# povsheild.net
KiCad netlist of a schematic drawn in EAGLE
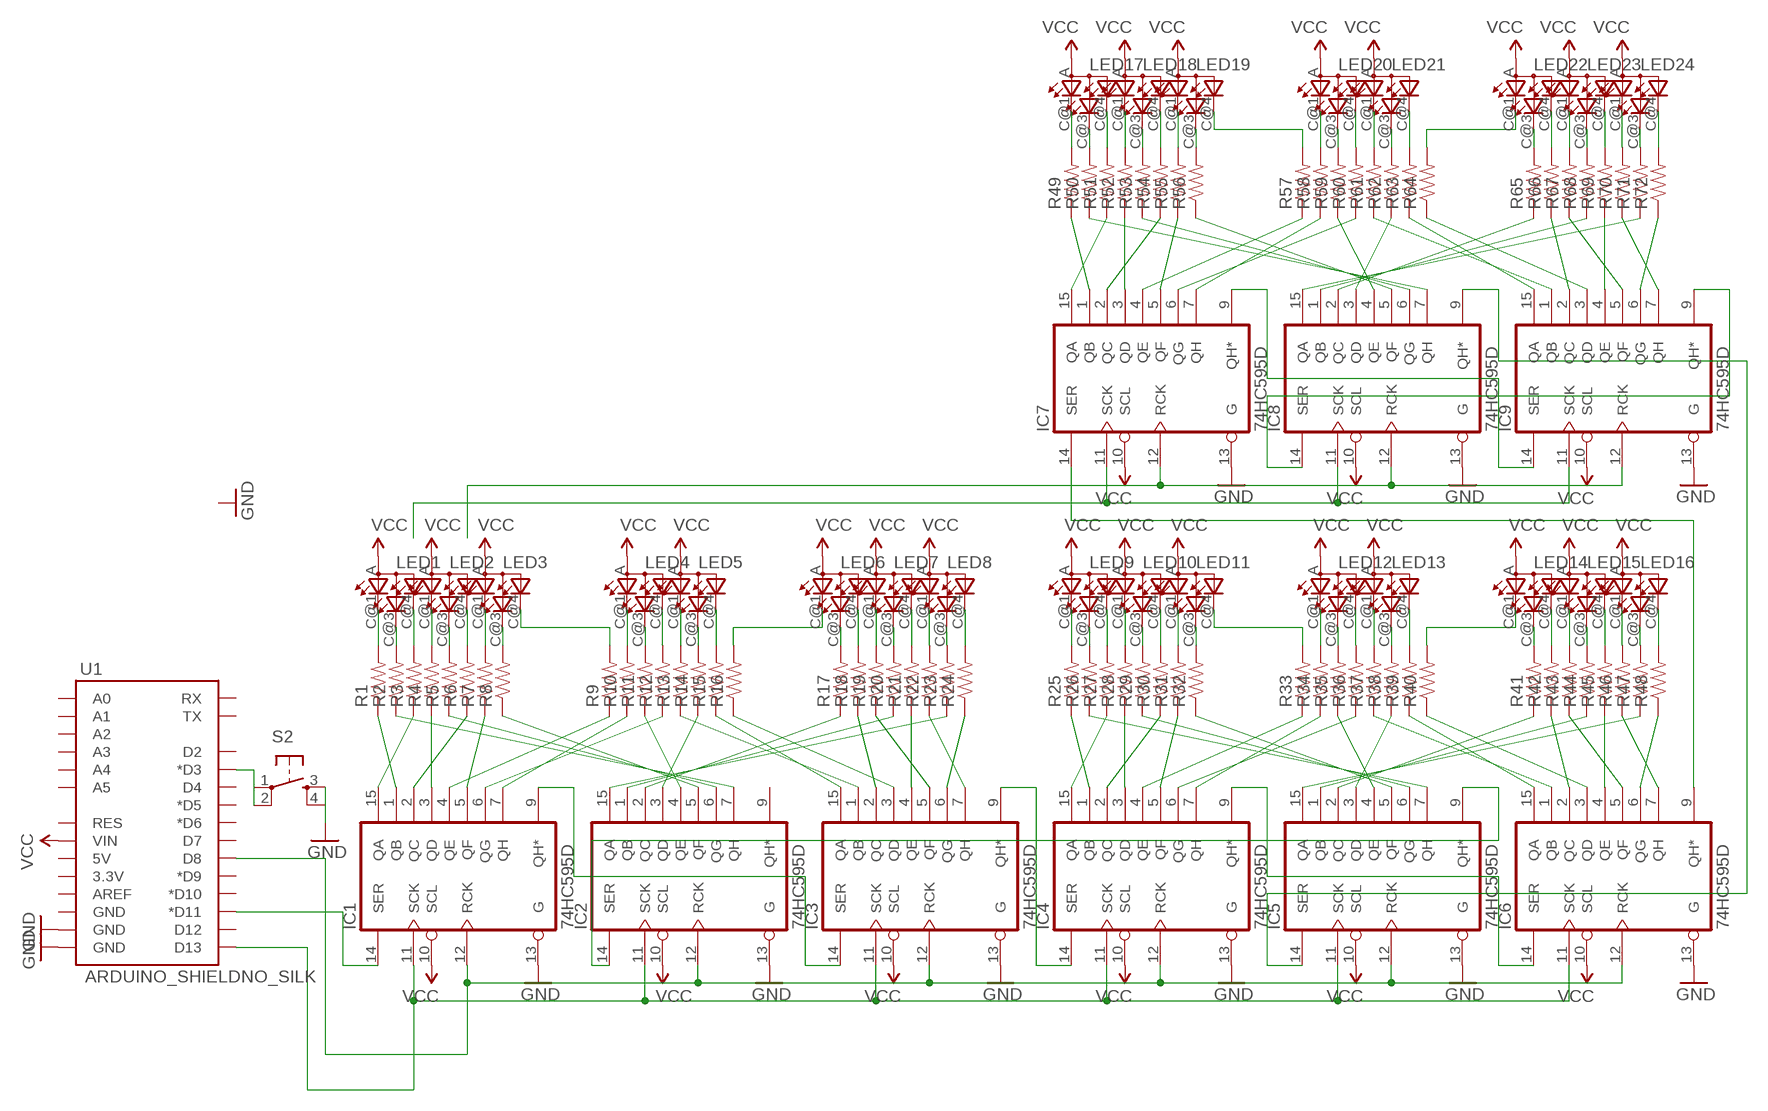
[diagram p0: schematic, sheet 1]

(export (version "E")
  (design (tool "Eeschema 10.0.6"))
  (components
    (comp (ref "IC1")
      (value "74HC595D")
      (footprint "eagle-import:SO16")
      (libsource (lib "eagle-import") (part "74595DHC"))
    )
    (comp (ref "IC2")
      (value "74HC595D")
      (footprint "eagle-import:SO16")
      (libsource (lib "eagle-import") (part "74595DHC"))
    )
    (comp (ref "IC3")
      (value "74HC595D")
      (footprint "eagle-import:SO16")
      (libsource (lib "eagle-import") (part "74595DHC"))
    )
    (comp (ref "IC4")
      (value "74HC595D")
      (footprint "eagle-import:SO16")
      (libsource (lib "eagle-import") (part "74595DHC"))
    )
    (comp (ref "IC5")
      (value "74HC595D")
      (footprint "eagle-import:SO16")
      (libsource (lib "eagle-import") (part "74595DHC"))
    )
    (comp (ref "IC6")
      (value "74HC595D")
      (footprint "eagle-import:SO16")
      (libsource (lib "eagle-import") (part "74595DHC"))
    )
    (comp (ref "IC7")
      (value "74HC595D")
      (footprint "eagle-import:SO16")
      (libsource (lib "eagle-import") (part "74595DHC"))
    )
    (comp (ref "IC8")
      (value "74HC595D")
      (footprint "eagle-import:SO16")
      (libsource (lib "eagle-import") (part "74595DHC"))
    )
    (comp (ref "IC9")
      (value "74HC595D")
      (footprint "eagle-import:SO16")
      (libsource (lib "eagle-import") (part "74595DHC"))
    )
    (comp (ref "LED1")
      (value "TOPLED-3P-LCC-4")
      (footprint "eagle-import:P-LCC-4")
      (libsource (lib "eagle-import") (part "TOPLED-3P-LCC-4"))
    )
    (comp (ref "LED2")
      (value "TOPLED-3P-LCC-4")
      (footprint "eagle-import:P-LCC-4")
      (libsource (lib "eagle-import") (part "TOPLED-3P-LCC-4"))
    )
    (comp (ref "LED3")
      (value "TOPLED-3P-LCC-4")
      (footprint "eagle-import:P-LCC-4")
      (libsource (lib "eagle-import") (part "TOPLED-3P-LCC-4"))
    )
    (comp (ref "LED4")
      (value "TOPLED-3P-LCC-4")
      (footprint "eagle-import:P-LCC-4")
      (libsource (lib "eagle-import") (part "TOPLED-3P-LCC-4"))
    )
    (comp (ref "LED5")
      (value "TOPLED-3P-LCC-4")
      (footprint "eagle-import:P-LCC-4")
      (libsource (lib "eagle-import") (part "TOPLED-3P-LCC-4"))
    )
    (comp (ref "LED6")
      (value "TOPLED-3P-LCC-4")
      (footprint "eagle-import:P-LCC-4")
      (libsource (lib "eagle-import") (part "TOPLED-3P-LCC-4"))
    )
    (comp (ref "LED7")
      (value "TOPLED-3P-LCC-4")
      (footprint "eagle-import:P-LCC-4")
      (libsource (lib "eagle-import") (part "TOPLED-3P-LCC-4"))
    )
    (comp (ref "LED8")
      (value "TOPLED-3P-LCC-4")
      (footprint "eagle-import:P-LCC-4")
      (libsource (lib "eagle-import") (part "TOPLED-3P-LCC-4"))
    )
    (comp (ref "LED9")
      (value "TOPLED-3P-LCC-4")
      (footprint "eagle-import:P-LCC-4")
      (libsource (lib "eagle-import") (part "TOPLED-3P-LCC-4"))
    )
    (comp (ref "LED10")
      (value "TOPLED-3P-LCC-4")
      (footprint "eagle-import:P-LCC-4")
      (libsource (lib "eagle-import") (part "TOPLED-3P-LCC-4"))
    )
    (comp (ref "LED11")
      (value "TOPLED-3P-LCC-4")
      (footprint "eagle-import:P-LCC-4")
      (libsource (lib "eagle-import") (part "TOPLED-3P-LCC-4"))
    )
    (comp (ref "LED12")
      (value "TOPLED-3P-LCC-4")
      (footprint "eagle-import:P-LCC-4")
      (libsource (lib "eagle-import") (part "TOPLED-3P-LCC-4"))
    )
    (comp (ref "LED13")
      (value "TOPLED-3P-LCC-4")
      (footprint "eagle-import:P-LCC-4")
      (libsource (lib "eagle-import") (part "TOPLED-3P-LCC-4"))
    )
    (comp (ref "LED14")
      (value "TOPLED-3P-LCC-4")
      (footprint "eagle-import:P-LCC-4")
      (libsource (lib "eagle-import") (part "TOPLED-3P-LCC-4"))
    )
    (comp (ref "LED15")
      (value "TOPLED-3P-LCC-4")
      (footprint "eagle-import:P-LCC-4")
      (libsource (lib "eagle-import") (part "TOPLED-3P-LCC-4"))
    )
    (comp (ref "LED16")
      (value "TOPLED-3P-LCC-4")
      (footprint "eagle-import:P-LCC-4")
      (libsource (lib "eagle-import") (part "TOPLED-3P-LCC-4"))
    )
    (comp (ref "LED17")
      (value "TOPLED-3P-LCC-4")
      (footprint "eagle-import:P-LCC-4")
      (libsource (lib "eagle-import") (part "TOPLED-3P-LCC-4"))
    )
    (comp (ref "LED18")
      (value "TOPLED-3P-LCC-4")
      (footprint "eagle-import:P-LCC-4")
      (libsource (lib "eagle-import") (part "TOPLED-3P-LCC-4"))
    )
    (comp (ref "LED19")
      (value "TOPLED-3P-LCC-4")
      (footprint "eagle-import:P-LCC-4")
      (libsource (lib "eagle-import") (part "TOPLED-3P-LCC-4"))
    )
    (comp (ref "LED20")
      (value "TOPLED-3P-LCC-4")
      (footprint "eagle-import:P-LCC-4")
      (libsource (lib "eagle-import") (part "TOPLED-3P-LCC-4"))
    )
    (comp (ref "LED21")
      (value "TOPLED-3P-LCC-4")
      (footprint "eagle-import:P-LCC-4")
      (libsource (lib "eagle-import") (part "TOPLED-3P-LCC-4"))
    )
    (comp (ref "LED22")
      (value "TOPLED-3P-LCC-4")
      (footprint "eagle-import:P-LCC-4")
      (libsource (lib "eagle-import") (part "TOPLED-3P-LCC-4"))
    )
    (comp (ref "LED23")
      (value "TOPLED-3P-LCC-4")
      (footprint "eagle-import:P-LCC-4")
      (libsource (lib "eagle-import") (part "TOPLED-3P-LCC-4"))
    )
    (comp (ref "LED24")
      (value "TOPLED-3P-LCC-4")
      (footprint "eagle-import:P-LCC-4")
      (libsource (lib "eagle-import") (part "TOPLED-3P-LCC-4"))
    )
    (comp (ref "R1")
      (value "RESISTOR0805-RES")
      (footprint "eagle-import:0805")
      (libsource (lib "eagle-import") (part "RESISTOR0805-RES"))
    )
    (comp (ref "R2")
      (value "RESISTOR0805-RES")
      (footprint "eagle-import:0805")
      (libsource (lib "eagle-import") (part "RESISTOR0805-RES"))
    )
    (comp (ref "R3")
      (value "RESISTOR0805-RES")
      (footprint "eagle-import:0805")
      (libsource (lib "eagle-import") (part "RESISTOR0805-RES"))
    )
    (comp (ref "R4")
      (value "RESISTOR0805-RES")
      (footprint "eagle-import:0805")
      (libsource (lib "eagle-import") (part "RESISTOR0805-RES"))
    )
    (comp (ref "R5")
      (value "RESISTOR0805-RES")
      (footprint "eagle-import:0805")
      (libsource (lib "eagle-import") (part "RESISTOR0805-RES"))
    )
    (comp (ref "R6")
      (value "RESISTOR0805-RES")
      (footprint "eagle-import:0805")
      (libsource (lib "eagle-import") (part "RESISTOR0805-RES"))
    )
    (comp (ref "R7")
      (value "RESISTOR0805-RES")
      (footprint "eagle-import:0805")
      (libsource (lib "eagle-import") (part "RESISTOR0805-RES"))
    )
    (comp (ref "R8")
      (value "RESISTOR0805-RES")
      (footprint "eagle-import:0805")
      (libsource (lib "eagle-import") (part "RESISTOR0805-RES"))
    )
    (comp (ref "R9")
      (value "RESISTOR0805-RES")
      (footprint "eagle-import:0805")
      (libsource (lib "eagle-import") (part "RESISTOR0805-RES"))
    )
    (comp (ref "R10")
      (value "RESISTOR0805-RES")
      (footprint "eagle-import:0805")
      (libsource (lib "eagle-import") (part "RESISTOR0805-RES"))
    )
    (comp (ref "R11")
      (value "RESISTOR0805-RES")
      (footprint "eagle-import:0805")
      (libsource (lib "eagle-import") (part "RESISTOR0805-RES"))
    )
    (comp (ref "R12")
      (value "RESISTOR0805-RES")
      (footprint "eagle-import:0805")
      (libsource (lib "eagle-import") (part "RESISTOR0805-RES"))
    )
    (comp (ref "R13")
      (value "RESISTOR0805-RES")
      (footprint "eagle-import:0805")
      (libsource (lib "eagle-import") (part "RESISTOR0805-RES"))
    )
    (comp (ref "R14")
      (value "RESISTOR0805-RES")
      (footprint "eagle-import:0805")
      (libsource (lib "eagle-import") (part "RESISTOR0805-RES"))
    )
    (comp (ref "R15")
      (value "RESISTOR0805-RES")
      (footprint "eagle-import:0805")
      (libsource (lib "eagle-import") (part "RESISTOR0805-RES"))
    )
    (comp (ref "R16")
      (value "RESISTOR0805-RES")
      (footprint "eagle-import:0805")
      (libsource (lib "eagle-import") (part "RESISTOR0805-RES"))
    )
    (comp (ref "R17")
      (value "RESISTOR0805-RES")
      (footprint "eagle-import:0805")
      (libsource (lib "eagle-import") (part "RESISTOR0805-RES"))
    )
    (comp (ref "R18")
      (value "RESISTOR0805-RES")
      (footprint "eagle-import:0805")
      (libsource (lib "eagle-import") (part "RESISTOR0805-RES"))
    )
    (comp (ref "R19")
      (value "RESISTOR0805-RES")
      (footprint "eagle-import:0805")
      (libsource (lib "eagle-import") (part "RESISTOR0805-RES"))
    )
    (comp (ref "R20")
      (value "RESISTOR0805-RES")
      (footprint "eagle-import:0805")
      (libsource (lib "eagle-import") (part "RESISTOR0805-RES"))
    )
    (comp (ref "R21")
      (value "RESISTOR0805-RES")
      (footprint "eagle-import:0805")
      (libsource (lib "eagle-import") (part "RESISTOR0805-RES"))
    )
    (comp (ref "R22")
      (value "RESISTOR0805-RES")
      (footprint "eagle-import:0805")
      (libsource (lib "eagle-import") (part "RESISTOR0805-RES"))
    )
    (comp (ref "R23")
      (value "RESISTOR0805-RES")
      (footprint "eagle-import:0805")
      (libsource (lib "eagle-import") (part "RESISTOR0805-RES"))
    )
    (comp (ref "R24")
      (value "RESISTOR0805-RES")
      (footprint "eagle-import:0805")
      (libsource (lib "eagle-import") (part "RESISTOR0805-RES"))
    )
    (comp (ref "R25")
      (value "RESISTOR0805-RES")
      (footprint "eagle-import:0805")
      (libsource (lib "eagle-import") (part "RESISTOR0805-RES"))
    )
    (comp (ref "R26")
      (value "RESISTOR0805-RES")
      (footprint "eagle-import:0805")
      (libsource (lib "eagle-import") (part "RESISTOR0805-RES"))
    )
    (comp (ref "R27")
      (value "RESISTOR0805-RES")
      (footprint "eagle-import:0805")
      (libsource (lib "eagle-import") (part "RESISTOR0805-RES"))
    )
    (comp (ref "R28")
      (value "RESISTOR0805-RES")
      (footprint "eagle-import:0805")
      (libsource (lib "eagle-import") (part "RESISTOR0805-RES"))
    )
    (comp (ref "R29")
      (value "RESISTOR0805-RES")
      (footprint "eagle-import:0805")
      (libsource (lib "eagle-import") (part "RESISTOR0805-RES"))
    )
    (comp (ref "R30")
      (value "RESISTOR0805-RES")
      (footprint "eagle-import:0805")
      (libsource (lib "eagle-import") (part "RESISTOR0805-RES"))
    )
    (comp (ref "R31")
      (value "RESISTOR0805-RES")
      (footprint "eagle-import:0805")
      (libsource (lib "eagle-import") (part "RESISTOR0805-RES"))
    )
    (comp (ref "R32")
      (value "RESISTOR0805-RES")
      (footprint "eagle-import:0805")
      (libsource (lib "eagle-import") (part "RESISTOR0805-RES"))
    )
    (comp (ref "R33")
      (value "RESISTOR0805-RES")
      (footprint "eagle-import:0805")
      (libsource (lib "eagle-import") (part "RESISTOR0805-RES"))
    )
    (comp (ref "R34")
      (value "RESISTOR0805-RES")
      (footprint "eagle-import:0805")
      (libsource (lib "eagle-import") (part "RESISTOR0805-RES"))
    )
    (comp (ref "R35")
      (value "RESISTOR0805-RES")
      (footprint "eagle-import:0805")
      (libsource (lib "eagle-import") (part "RESISTOR0805-RES"))
    )
    (comp (ref "R36")
      (value "RESISTOR0805-RES")
      (footprint "eagle-import:0805")
      (libsource (lib "eagle-import") (part "RESISTOR0805-RES"))
    )
    (comp (ref "R37")
      (value "RESISTOR0805-RES")
      (footprint "eagle-import:0805")
      (libsource (lib "eagle-import") (part "RESISTOR0805-RES"))
    )
    (comp (ref "R38")
      (value "RESISTOR0805-RES")
      (footprint "eagle-import:0805")
      (libsource (lib "eagle-import") (part "RESISTOR0805-RES"))
    )
    (comp (ref "R39")
      (value "RESISTOR0805-RES")
      (footprint "eagle-import:0805")
      (libsource (lib "eagle-import") (part "RESISTOR0805-RES"))
    )
    (comp (ref "R40")
      (value "RESISTOR0805-RES")
      (footprint "eagle-import:0805")
      (libsource (lib "eagle-import") (part "RESISTOR0805-RES"))
    )
    (comp (ref "R41")
      (value "RESISTOR0805-RES")
      (footprint "eagle-import:0805")
      (libsource (lib "eagle-import") (part "RESISTOR0805-RES"))
    )
    (comp (ref "R42")
      (value "RESISTOR0805-RES")
      (footprint "eagle-import:0805")
      (libsource (lib "eagle-import") (part "RESISTOR0805-RES"))
    )
    (comp (ref "R43")
      (value "RESISTOR0805-RES")
      (footprint "eagle-import:0805")
      (libsource (lib "eagle-import") (part "RESISTOR0805-RES"))
    )
    (comp (ref "R44")
      (value "RESISTOR0805-RES")
      (footprint "eagle-import:0805")
      (libsource (lib "eagle-import") (part "RESISTOR0805-RES"))
    )
    (comp (ref "R45")
      (value "RESISTOR0805-RES")
      (footprint "eagle-import:0805")
      (libsource (lib "eagle-import") (part "RESISTOR0805-RES"))
    )
    (comp (ref "R46")
      (value "RESISTOR0805-RES")
      (footprint "eagle-import:0805")
      (libsource (lib "eagle-import") (part "RESISTOR0805-RES"))
    )
    (comp (ref "R47")
      (value "RESISTOR0805-RES")
      (footprint "eagle-import:0805")
      (libsource (lib "eagle-import") (part "RESISTOR0805-RES"))
    )
    (comp (ref "R48")
      (value "RESISTOR0805-RES")
      (footprint "eagle-import:0805")
      (libsource (lib "eagle-import") (part "RESISTOR0805-RES"))
    )
    (comp (ref "R49")
      (value "RESISTOR0805-RES")
      (footprint "eagle-import:0805")
      (libsource (lib "eagle-import") (part "RESISTOR0805-RES"))
    )
    (comp (ref "R50")
      (value "RESISTOR0805-RES")
      (footprint "eagle-import:0805")
      (libsource (lib "eagle-import") (part "RESISTOR0805-RES"))
    )
    (comp (ref "R51")
      (value "RESISTOR0805-RES")
      (footprint "eagle-import:0805")
      (libsource (lib "eagle-import") (part "RESISTOR0805-RES"))
    )
    (comp (ref "R52")
      (value "RESISTOR0805-RES")
      (footprint "eagle-import:0805")
      (libsource (lib "eagle-import") (part "RESISTOR0805-RES"))
    )
    (comp (ref "R53")
      (value "RESISTOR0805-RES")
      (footprint "eagle-import:0805")
      (libsource (lib "eagle-import") (part "RESISTOR0805-RES"))
    )
    (comp (ref "R54")
      (value "RESISTOR0805-RES")
      (footprint "eagle-import:0805")
      (libsource (lib "eagle-import") (part "RESISTOR0805-RES"))
    )
    (comp (ref "R55")
      (value "RESISTOR0805-RES")
      (footprint "eagle-import:0805")
      (libsource (lib "eagle-import") (part "RESISTOR0805-RES"))
    )
    (comp (ref "R56")
      (value "RESISTOR0805-RES")
      (footprint "eagle-import:0805")
      (libsource (lib "eagle-import") (part "RESISTOR0805-RES"))
    )
    (comp (ref "R57")
      (value "RESISTOR0805-RES")
      (footprint "eagle-import:0805")
      (libsource (lib "eagle-import") (part "RESISTOR0805-RES"))
    )
    (comp (ref "R58")
      (value "RESISTOR0805-RES")
      (footprint "eagle-import:0805")
      (libsource (lib "eagle-import") (part "RESISTOR0805-RES"))
    )
    (comp (ref "R59")
      (value "RESISTOR0805-RES")
      (footprint "eagle-import:0805")
      (libsource (lib "eagle-import") (part "RESISTOR0805-RES"))
    )
    (comp (ref "R60")
      (value "RESISTOR0805-RES")
      (footprint "eagle-import:0805")
      (libsource (lib "eagle-import") (part "RESISTOR0805-RES"))
    )
    (comp (ref "R61")
      (value "RESISTOR0805-RES")
      (footprint "eagle-import:0805")
      (libsource (lib "eagle-import") (part "RESISTOR0805-RES"))
    )
    (comp (ref "R62")
      (value "RESISTOR0805-RES")
      (footprint "eagle-import:0805")
      (libsource (lib "eagle-import") (part "RESISTOR0805-RES"))
    )
    (comp (ref "R63")
      (value "RESISTOR0805-RES")
      (footprint "eagle-import:0805")
      (libsource (lib "eagle-import") (part "RESISTOR0805-RES"))
    )
    (comp (ref "R64")
      (value "RESISTOR0805-RES")
      (footprint "eagle-import:0805")
      (libsource (lib "eagle-import") (part "RESISTOR0805-RES"))
    )
    (comp (ref "R65")
      (value "RESISTOR0805-RES")
      (footprint "eagle-import:0805")
      (libsource (lib "eagle-import") (part "RESISTOR0805-RES"))
    )
    (comp (ref "R66")
      (value "RESISTOR0805-RES")
      (footprint "eagle-import:0805")
      (libsource (lib "eagle-import") (part "RESISTOR0805-RES"))
    )
    (comp (ref "R67")
      (value "RESISTOR0805-RES")
      (footprint "eagle-import:0805")
      (libsource (lib "eagle-import") (part "RESISTOR0805-RES"))
    )
    (comp (ref "R68")
      (value "RESISTOR0805-RES")
      (footprint "eagle-import:0805")
      (libsource (lib "eagle-import") (part "RESISTOR0805-RES"))
    )
    (comp (ref "R69")
      (value "RESISTOR0805-RES")
      (footprint "eagle-import:0805")
      (libsource (lib "eagle-import") (part "RESISTOR0805-RES"))
    )
    (comp (ref "R70")
      (value "RESISTOR0805-RES")
      (footprint "eagle-import:0805")
      (libsource (lib "eagle-import") (part "RESISTOR0805-RES"))
    )
    (comp (ref "R71")
      (value "RESISTOR0805-RES")
      (footprint "eagle-import:0805")
      (libsource (lib "eagle-import") (part "RESISTOR0805-RES"))
    )
    (comp (ref "R72")
      (value "RESISTOR0805-RES")
      (footprint "eagle-import:0805")
      (libsource (lib "eagle-import") (part "RESISTOR0805-RES"))
    )
    (comp (ref "S2")
      (value "TAC_SWITCHSMD")
      (footprint "eagle-import:TACTILE_SWITCH_SMD")
      (libsource (lib "eagle-import") (part "TAC_SWITCHSMD"))
    )
    (comp (ref "U1")
      (value "ARDUINO_SHIELDNO_SILK")
      (footprint "eagle-import:DUEMILANOVE_VIAS")
      (libsource (lib "eagle-import") (part "ARDUINO_SHIELDNO_SILK"))
    )
  )
  (nets
    (net (code "1") (name "/LATCH") (class "Default")
      (node (ref "IC1") (pin "12") (pinfunction "RCK_12") (pintype "input"))
      (node (ref "IC2") (pin "12") (pinfunction "RCK_12") (pintype "input"))
      (node (ref "IC3") (pin "12") (pinfunction "RCK_12") (pintype "input"))
      (node (ref "IC4") (pin "12") (pinfunction "RCK_12") (pintype "input"))
      (node (ref "IC5") (pin "12") (pinfunction "RCK_12") (pintype "input"))
      (node (ref "IC6") (pin "12") (pinfunction "RCK_12") (pintype "input"))
      (node (ref "IC7") (pin "12") (pinfunction "RCK_12") (pintype "input"))
      (node (ref "IC8") (pin "12") (pinfunction "RCK_12") (pintype "input"))
      (node (ref "IC9") (pin "12") (pinfunction "RCK_12") (pintype "input"))
      (node (ref "U1") (pin "D8") (pinfunction "D8_D8") (pintype "bidirectional"))
    )
    (net (code "2") (name "/SCK") (class "Default")
      (node (ref "IC1") (pin "11") (pinfunction "SCK_11") (pintype "input"))
      (node (ref "IC2") (pin "11") (pinfunction "SCK_11") (pintype "input"))
      (node (ref "IC3") (pin "11") (pinfunction "SCK_11") (pintype "input"))
      (node (ref "IC4") (pin "11") (pinfunction "SCK_11") (pintype "input"))
      (node (ref "IC5") (pin "11") (pinfunction "SCK_11") (pintype "input"))
      (node (ref "IC6") (pin "11") (pinfunction "SCK_11") (pintype "input"))
      (node (ref "IC7") (pin "11") (pinfunction "SCK_11") (pintype "input"))
      (node (ref "IC8") (pin "11") (pinfunction "SCK_11") (pintype "input"))
      (node (ref "IC9") (pin "11") (pinfunction "SCK_11") (pintype "input"))
      (node (ref "U1") (pin "D13") (pinfunction "D13_D13") (pintype "bidirectional"))
    )
    (net (code "3") (name "GND") (class "Default")
      (node (ref "IC1") (pin "13") (pinfunction "G_13") (pintype "input"))
      (node (ref "IC2") (pin "13") (pinfunction "G_13") (pintype "input"))
      (node (ref "IC3") (pin "13") (pinfunction "G_13") (pintype "input"))
      (node (ref "IC4") (pin "13") (pinfunction "G_13") (pintype "input"))
      (node (ref "IC5") (pin "13") (pinfunction "G_13") (pintype "input"))
      (node (ref "IC6") (pin "13") (pinfunction "G_13") (pintype "input"))
      (node (ref "IC7") (pin "13") (pinfunction "G_13") (pintype "input"))
      (node (ref "IC8") (pin "13") (pinfunction "G_13") (pintype "input"))
      (node (ref "IC9") (pin "13") (pinfunction "G_13") (pintype "input"))
      (node (ref "S2") (pin "3") (pinfunction "3_3") (pintype "passive"))
      (node (ref "S2") (pin "4") (pinfunction "4_4") (pintype "passive"))
      (node (ref "U1") (pin "GND@0") (pinfunction "GND_GND@0") (pintype "bidirectional"))
      (node (ref "U1") (pin "GND@1") (pinfunction "GND_GND@1") (pintype "bidirectional"))
    )
    (net (code "4") (name "Net-(IC1A-QA)") (class "Default")
      (node (ref "IC1") (pin "15") (pinfunction "QA_15") (pintype "tri_state"))
      (node (ref "R3") (pin "1") (pinfunction "1_1") (pintype "passive"))
    )
    (net (code "5") (name "Net-(IC1A-QB)") (class "Default")
      (node (ref "IC1") (pin "1") (pinfunction "QB_1") (pintype "tri_state"))
      (node (ref "R1") (pin "1") (pinfunction "1_1") (pintype "passive"))
    )
    (net (code "6") (name "Net-(IC1A-QC)") (class "Default")
      (node (ref "IC1") (pin "2") (pinfunction "QC_2") (pintype "tri_state"))
      (node (ref "R6") (pin "1") (pinfunction "1_1") (pintype "passive"))
    )
    (net (code "7") (name "Net-(IC1A-QD)") (class "Default")
      (node (ref "IC1") (pin "3") (pinfunction "QD_3") (pintype "tri_state"))
      (node (ref "R4") (pin "1") (pinfunction "1_1") (pintype "passive"))
    )
    (net (code "8") (name "Net-(IC1A-QE)") (class "Default")
      (node (ref "IC1") (pin "4") (pinfunction "QE_4") (pintype "tri_state"))
      (node (ref "R9") (pin "1") (pinfunction "1_1") (pintype "passive"))
    )
    (net (code "9") (name "Net-(IC1A-QF)") (class "Default")
      (node (ref "IC1") (pin "5") (pinfunction "QF_5") (pintype "tri_state"))
      (node (ref "R7") (pin "1") (pinfunction "1_1") (pintype "passive"))
    )
    (net (code "10") (name "Net-(IC1A-QG)") (class "Default")
      (node (ref "IC1") (pin "6") (pinfunction "QG_6") (pintype "tri_state"))
      (node (ref "R12") (pin "1") (pinfunction "1_1") (pintype "passive"))
    )
    (net (code "11") (name "Net-(IC1A-QH)") (class "Default")
      (node (ref "IC1") (pin "7") (pinfunction "QH_7") (pintype "tri_state"))
      (node (ref "R10") (pin "1") (pinfunction "1_1") (pintype "passive"))
    )
    (net (code "12") (name "Net-(IC1A-QH*)") (class "Default")
      (node (ref "IC1") (pin "9") (pinfunction "QH*_9") (pintype "tri_state"))
      (node (ref "IC3") (pin "14") (pinfunction "SER_14") (pintype "input"))
    )
    (net (code "13") (name "Net-(IC1A-SER)") (class "Default")
      (node (ref "IC1") (pin "14") (pinfunction "SER_14") (pintype "input"))
      (node (ref "U1") (pin "D11") (pinfunction "*D11_D11") (pintype "bidirectional"))
    )
    (net (code "14") (name "Net-(IC2A-QA)") (class "Default")
      (node (ref "IC2") (pin "15") (pinfunction "QA_15") (pintype "tri_state"))
      (node (ref "R23") (pin "1") (pinfunction "1_1") (pintype "passive"))
    )
    (net (code "15") (name "Net-(IC2A-QB)") (class "Default")
      (node (ref "IC2") (pin "1") (pinfunction "QB_1") (pintype "tri_state"))
      (node (ref "R20") (pin "1") (pinfunction "1_1") (pintype "passive"))
    )
    (net (code "16") (name "Net-(IC2A-QC)") (class "Default")
      (node (ref "IC2") (pin "2") (pinfunction "QC_2") (pintype "tri_state"))
      (node (ref "R17") (pin "1") (pinfunction "1_1") (pintype "passive"))
    )
    (net (code "17") (name "Net-(IC2A-QD)") (class "Default")
      (node (ref "IC2") (pin "3") (pinfunction "QD_3") (pintype "tri_state"))
      (node (ref "R14") (pin "1") (pinfunction "1_1") (pintype "passive"))
    )
    (net (code "18") (name "Net-(IC2A-QE)") (class "Default")
      (node (ref "IC2") (pin "4") (pinfunction "QE_4") (pintype "tri_state"))
      (node (ref "R11") (pin "1") (pinfunction "1_1") (pintype "passive"))
    )
    (net (code "19") (name "Net-(IC2A-QF)") (class "Default")
      (node (ref "IC2") (pin "5") (pinfunction "QF_5") (pintype "tri_state"))
      (node (ref "R8") (pin "1") (pinfunction "1_1") (pintype "passive"))
    )
    (net (code "20") (name "Net-(IC2A-QG)") (class "Default")
      (node (ref "IC2") (pin "6") (pinfunction "QG_6") (pintype "tri_state"))
      (node (ref "R5") (pin "1") (pinfunction "1_1") (pintype "passive"))
    )
    (net (code "21") (name "Net-(IC2A-QH)") (class "Default")
      (node (ref "IC2") (pin "7") (pinfunction "QH_7") (pintype "tri_state"))
      (node (ref "R2") (pin "1") (pinfunction "1_1") (pintype "passive"))
    )
    (net (code "22") (name "Net-(IC2A-SER)") (class "Default")
      (node (ref "IC2") (pin "14") (pinfunction "SER_14") (pintype "input"))
      (node (ref "IC5") (pin "9") (pinfunction "QH*_9") (pintype "tri_state"))
    )
    (net (code "23") (name "Net-(IC3A-QA)") (class "Default")
      (node (ref "IC3") (pin "15") (pinfunction "QA_15") (pintype "tri_state"))
      (node (ref "R15") (pin "1") (pinfunction "1_1") (pintype "passive"))
    )
    (net (code "24") (name "Net-(IC3A-QB)") (class "Default")
      (node (ref "IC3") (pin "1") (pinfunction "QB_1") (pintype "tri_state"))
      (node (ref "R13") (pin "1") (pinfunction "1_1") (pintype "passive"))
    )
    (net (code "25") (name "Net-(IC3A-QC)") (class "Default")
      (node (ref "IC3") (pin "2") (pinfunction "QC_2") (pintype "tri_state"))
      (node (ref "R18") (pin "1") (pinfunction "1_1") (pintype "passive"))
    )
    (net (code "26") (name "Net-(IC3A-QD)") (class "Default")
      (node (ref "IC3") (pin "3") (pinfunction "QD_3") (pintype "tri_state"))
      (node (ref "R16") (pin "1") (pinfunction "1_1") (pintype "passive"))
    )
    (net (code "27") (name "Net-(IC3A-QE)") (class "Default")
      (node (ref "IC3") (pin "4") (pinfunction "QE_4") (pintype "tri_state"))
      (node (ref "R21") (pin "1") (pinfunction "1_1") (pintype "passive"))
    )
    (net (code "28") (name "Net-(IC3A-QF)") (class "Default")
      (node (ref "IC3") (pin "5") (pinfunction "QF_5") (pintype "tri_state"))
      (node (ref "R19") (pin "1") (pinfunction "1_1") (pintype "passive"))
    )
    (net (code "29") (name "Net-(IC3A-QG)") (class "Default")
      (node (ref "IC3") (pin "6") (pinfunction "QG_6") (pintype "tri_state"))
      (node (ref "R24") (pin "1") (pinfunction "1_1") (pintype "passive"))
    )
    (net (code "30") (name "Net-(IC3A-QH)") (class "Default")
      (node (ref "IC3") (pin "7") (pinfunction "QH_7") (pintype "tri_state"))
      (node (ref "R22") (pin "1") (pinfunction "1_1") (pintype "passive"))
    )
    (net (code "31") (name "Net-(IC3A-QH*)") (class "Default")
      (node (ref "IC3") (pin "9") (pinfunction "QH*_9") (pintype "tri_state"))
      (node (ref "IC4") (pin "14") (pinfunction "SER_14") (pintype "input"))
    )
    (net (code "32") (name "Net-(IC4A-QA)") (class "Default")
      (node (ref "IC4") (pin "15") (pinfunction "QA_15") (pintype "tri_state"))
      (node (ref "R27") (pin "1") (pinfunction "1_1") (pintype "passive"))
    )
    (net (code "33") (name "Net-(IC4A-QB)") (class "Default")
      (node (ref "IC4") (pin "1") (pinfunction "QB_1") (pintype "tri_state"))
      (node (ref "R25") (pin "1") (pinfunction "1_1") (pintype "passive"))
    )
    (net (code "34") (name "Net-(IC4A-QC)") (class "Default")
      (node (ref "IC4") (pin "2") (pinfunction "QC_2") (pintype "tri_state"))
      (node (ref "R30") (pin "1") (pinfunction "1_1") (pintype "passive"))
    )
    (net (code "35") (name "Net-(IC4A-QD)") (class "Default")
      (node (ref "IC4") (pin "3") (pinfunction "QD_3") (pintype "tri_state"))
      (node (ref "R28") (pin "1") (pinfunction "1_1") (pintype "passive"))
    )
    (net (code "36") (name "Net-(IC4A-QE)") (class "Default")
      (node (ref "IC4") (pin "4") (pinfunction "QE_4") (pintype "tri_state"))
      (node (ref "R33") (pin "1") (pinfunction "1_1") (pintype "passive"))
    )
    (net (code "37") (name "Net-(IC4A-QF)") (class "Default")
      (node (ref "IC4") (pin "5") (pinfunction "QF_5") (pintype "tri_state"))
      (node (ref "R31") (pin "1") (pinfunction "1_1") (pintype "passive"))
    )
    (net (code "38") (name "Net-(IC4A-QG)") (class "Default")
      (node (ref "IC4") (pin "6") (pinfunction "QG_6") (pintype "tri_state"))
      (node (ref "R36") (pin "1") (pinfunction "1_1") (pintype "passive"))
    )
    (net (code "39") (name "Net-(IC4A-QH)") (class "Default")
      (node (ref "IC4") (pin "7") (pinfunction "QH_7") (pintype "tri_state"))
      (node (ref "R34") (pin "1") (pinfunction "1_1") (pintype "passive"))
    )
    (net (code "40") (name "Net-(IC4A-QH*)") (class "Default")
      (node (ref "IC4") (pin "9") (pinfunction "QH*_9") (pintype "tri_state"))
      (node (ref "IC6") (pin "14") (pinfunction "SER_14") (pintype "input"))
    )
    (net (code "41") (name "Net-(IC5A-QA)") (class "Default")
      (node (ref "IC5") (pin "15") (pinfunction "QA_15") (pintype "tri_state"))
      (node (ref "R47") (pin "1") (pinfunction "1_1") (pintype "passive"))
    )
    (net (code "42") (name "Net-(IC5A-QB)") (class "Default")
      (node (ref "IC5") (pin "1") (pinfunction "QB_1") (pintype "tri_state"))
      (node (ref "R44") (pin "1") (pinfunction "1_1") (pintype "passive"))
    )
    (net (code "43") (name "Net-(IC5A-QC)") (class "Default")
      (node (ref "IC5") (pin "2") (pinfunction "QC_2") (pintype "tri_state"))
      (node (ref "R41") (pin "1") (pinfunction "1_1") (pintype "passive"))
    )
    (net (code "44") (name "Net-(IC5A-QD)") (class "Default")
      (node (ref "IC5") (pin "3") (pinfunction "QD_3") (pintype "tri_state"))
      (node (ref "R38") (pin "1") (pinfunction "1_1") (pintype "passive"))
    )
    (net (code "45") (name "Net-(IC5A-QE)") (class "Default")
      (node (ref "IC5") (pin "4") (pinfunction "QE_4") (pintype "tri_state"))
      (node (ref "R35") (pin "1") (pinfunction "1_1") (pintype "passive"))
    )
    (net (code "46") (name "Net-(IC5A-QF)") (class "Default")
      (node (ref "IC5") (pin "5") (pinfunction "QF_5") (pintype "tri_state"))
      (node (ref "R32") (pin "1") (pinfunction "1_1") (pintype "passive"))
    )
    (net (code "47") (name "Net-(IC5A-QG)") (class "Default")
      (node (ref "IC5") (pin "6") (pinfunction "QG_6") (pintype "tri_state"))
      (node (ref "R29") (pin "1") (pinfunction "1_1") (pintype "passive"))
    )
    (net (code "48") (name "Net-(IC5A-QH)") (class "Default")
      (node (ref "IC5") (pin "7") (pinfunction "QH_7") (pintype "tri_state"))
      (node (ref "R26") (pin "1") (pinfunction "1_1") (pintype "passive"))
    )
    (net (code "49") (name "Net-(IC5A-SER)") (class "Default")
      (node (ref "IC5") (pin "14") (pinfunction "SER_14") (pintype "input"))
      (node (ref "IC8") (pin "9") (pinfunction "QH*_9") (pintype "tri_state"))
    )
    (net (code "50") (name "Net-(IC6A-QA)") (class "Default")
      (node (ref "IC6") (pin "15") (pinfunction "QA_15") (pintype "tri_state"))
      (node (ref "R39") (pin "1") (pinfunction "1_1") (pintype "passive"))
    )
    (net (code "51") (name "Net-(IC6A-QB)") (class "Default")
      (node (ref "IC6") (pin "1") (pinfunction "QB_1") (pintype "tri_state"))
      (node (ref "R37") (pin "1") (pinfunction "1_1") (pintype "passive"))
    )
    (net (code "52") (name "Net-(IC6A-QC)") (class "Default")
      (node (ref "IC6") (pin "2") (pinfunction "QC_2") (pintype "tri_state"))
      (node (ref "R42") (pin "1") (pinfunction "1_1") (pintype "passive"))
    )
    (net (code "53") (name "Net-(IC6A-QD)") (class "Default")
      (node (ref "IC6") (pin "3") (pinfunction "QD_3") (pintype "tri_state"))
      (node (ref "R40") (pin "1") (pinfunction "1_1") (pintype "passive"))
    )
    (net (code "54") (name "Net-(IC6A-QE)") (class "Default")
      (node (ref "IC6") (pin "4") (pinfunction "QE_4") (pintype "tri_state"))
      (node (ref "R45") (pin "1") (pinfunction "1_1") (pintype "passive"))
    )
    (net (code "55") (name "Net-(IC6A-QF)") (class "Default")
      (node (ref "IC6") (pin "5") (pinfunction "QF_5") (pintype "tri_state"))
      (node (ref "R43") (pin "1") (pinfunction "1_1") (pintype "passive"))
    )
    (net (code "56") (name "Net-(IC6A-QG)") (class "Default")
      (node (ref "IC6") (pin "6") (pinfunction "QG_6") (pintype "tri_state"))
      (node (ref "R48") (pin "1") (pinfunction "1_1") (pintype "passive"))
    )
    (net (code "57") (name "Net-(IC6A-QH)") (class "Default")
      (node (ref "IC6") (pin "7") (pinfunction "QH_7") (pintype "tri_state"))
      (node (ref "R46") (pin "1") (pinfunction "1_1") (pintype "passive"))
    )
    (net (code "58") (name "Net-(IC6A-QH*)") (class "Default")
      (node (ref "IC6") (pin "9") (pinfunction "QH*_9") (pintype "tri_state"))
      (node (ref "IC7") (pin "14") (pinfunction "SER_14") (pintype "input"))
    )
    (net (code "59") (name "Net-(IC7A-QA)") (class "Default")
      (node (ref "IC7") (pin "15") (pinfunction "QA_15") (pintype "tri_state"))
      (node (ref "R51") (pin "1") (pinfunction "1_1") (pintype "passive"))
    )
    (net (code "60") (name "Net-(IC7A-QB)") (class "Default")
      (node (ref "IC7") (pin "1") (pinfunction "QB_1") (pintype "tri_state"))
      (node (ref "R49") (pin "1") (pinfunction "1_1") (pintype "passive"))
    )
    (net (code "61") (name "Net-(IC7A-QC)") (class "Default")
      (node (ref "IC7") (pin "2") (pinfunction "QC_2") (pintype "tri_state"))
      (node (ref "R54") (pin "1") (pinfunction "1_1") (pintype "passive"))
    )
    (net (code "62") (name "Net-(IC7A-QD)") (class "Default")
      (node (ref "IC7") (pin "3") (pinfunction "QD_3") (pintype "tri_state"))
      (node (ref "R52") (pin "1") (pinfunction "1_1") (pintype "passive"))
    )
    (net (code "63") (name "Net-(IC7A-QE)") (class "Default")
      (node (ref "IC7") (pin "4") (pinfunction "QE_4") (pintype "tri_state"))
      (node (ref "R57") (pin "1") (pinfunction "1_1") (pintype "passive"))
    )
    (net (code "64") (name "Net-(IC7A-QF)") (class "Default")
      (node (ref "IC7") (pin "5") (pinfunction "QF_5") (pintype "tri_state"))
      (node (ref "R55") (pin "1") (pinfunction "1_1") (pintype "passive"))
    )
    (net (code "65") (name "Net-(IC7A-QG)") (class "Default")
      (node (ref "IC7") (pin "6") (pinfunction "QG_6") (pintype "tri_state"))
      (node (ref "R60") (pin "1") (pinfunction "1_1") (pintype "passive"))
    )
    (net (code "66") (name "Net-(IC7A-QH)") (class "Default")
      (node (ref "IC7") (pin "7") (pinfunction "QH_7") (pintype "tri_state"))
      (node (ref "R58") (pin "1") (pinfunction "1_1") (pintype "passive"))
    )
    (net (code "67") (name "Net-(IC7A-QH*)") (class "Default")
      (node (ref "IC7") (pin "9") (pinfunction "QH*_9") (pintype "tri_state"))
      (node (ref "IC9") (pin "14") (pinfunction "SER_14") (pintype "input"))
    )
    (net (code "68") (name "Net-(IC8A-QA)") (class "Default")
      (node (ref "IC8") (pin "15") (pinfunction "QA_15") (pintype "tri_state"))
      (node (ref "R71") (pin "1") (pinfunction "1_1") (pintype "passive"))
    )
    (net (code "69") (name "Net-(IC8A-QB)") (class "Default")
      (node (ref "IC8") (pin "1") (pinfunction "QB_1") (pintype "tri_state"))
      (node (ref "R68") (pin "1") (pinfunction "1_1") (pintype "passive"))
    )
    (net (code "70") (name "Net-(IC8A-QC)") (class "Default")
      (node (ref "IC8") (pin "2") (pinfunction "QC_2") (pintype "tri_state"))
      (node (ref "R65") (pin "1") (pinfunction "1_1") (pintype "passive"))
    )
    (net (code "71") (name "Net-(IC8A-QD)") (class "Default")
      (node (ref "IC8") (pin "3") (pinfunction "QD_3") (pintype "tri_state"))
      (node (ref "R62") (pin "1") (pinfunction "1_1") (pintype "passive"))
    )
    (net (code "72") (name "Net-(IC8A-QE)") (class "Default")
      (node (ref "IC8") (pin "4") (pinfunction "QE_4") (pintype "tri_state"))
      (node (ref "R59") (pin "1") (pinfunction "1_1") (pintype "passive"))
    )
    (net (code "73") (name "Net-(IC8A-QF)") (class "Default")
      (node (ref "IC8") (pin "5") (pinfunction "QF_5") (pintype "tri_state"))
      (node (ref "R56") (pin "1") (pinfunction "1_1") (pintype "passive"))
    )
    (net (code "74") (name "Net-(IC8A-QG)") (class "Default")
      (node (ref "IC8") (pin "6") (pinfunction "QG_6") (pintype "tri_state"))
      (node (ref "R53") (pin "1") (pinfunction "1_1") (pintype "passive"))
    )
    (net (code "75") (name "Net-(IC8A-QH)") (class "Default")
      (node (ref "IC8") (pin "7") (pinfunction "QH_7") (pintype "tri_state"))
      (node (ref "R50") (pin "1") (pinfunction "1_1") (pintype "passive"))
    )
    (net (code "76") (name "Net-(IC8A-SER)") (class "Default")
      (node (ref "IC8") (pin "14") (pinfunction "SER_14") (pintype "input"))
      (node (ref "IC9") (pin "9") (pinfunction "QH*_9") (pintype "tri_state"))
    )
    (net (code "77") (name "Net-(IC9A-QA)") (class "Default")
      (node (ref "IC9") (pin "15") (pinfunction "QA_15") (pintype "tri_state"))
      (node (ref "R63") (pin "1") (pinfunction "1_1") (pintype "passive"))
    )
    (net (code "78") (name "Net-(IC9A-QB)") (class "Default")
      (node (ref "IC9") (pin "1") (pinfunction "QB_1") (pintype "tri_state"))
      (node (ref "R61") (pin "1") (pinfunction "1_1") (pintype "passive"))
    )
    (net (code "79") (name "Net-(IC9A-QC)") (class "Default")
      (node (ref "IC9") (pin "2") (pinfunction "QC_2") (pintype "tri_state"))
      (node (ref "R66") (pin "1") (pinfunction "1_1") (pintype "passive"))
    )
    (net (code "80") (name "Net-(IC9A-QD)") (class "Default")
      (node (ref "IC9") (pin "3") (pinfunction "QD_3") (pintype "tri_state"))
      (node (ref "R64") (pin "1") (pinfunction "1_1") (pintype "passive"))
    )
    (net (code "81") (name "Net-(IC9A-QE)") (class "Default")
      (node (ref "IC9") (pin "4") (pinfunction "QE_4") (pintype "tri_state"))
      (node (ref "R69") (pin "1") (pinfunction "1_1") (pintype "passive"))
    )
    (net (code "82") (name "Net-(IC9A-QF)") (class "Default")
      (node (ref "IC9") (pin "5") (pinfunction "QF_5") (pintype "tri_state"))
      (node (ref "R67") (pin "1") (pinfunction "1_1") (pintype "passive"))
    )
    (net (code "83") (name "Net-(IC9A-QG)") (class "Default")
      (node (ref "IC9") (pin "6") (pinfunction "QG_6") (pintype "tri_state"))
      (node (ref "R72") (pin "1") (pinfunction "1_1") (pintype "passive"))
    )
    (net (code "84") (name "Net-(IC9A-QH)") (class "Default")
      (node (ref "IC9") (pin "7") (pinfunction "QH_7") (pintype "tri_state"))
      (node (ref "R70") (pin "1") (pinfunction "1_1") (pintype "passive"))
    )
    (net (code "85") (name "Net-(LED1-CBLUE)") (class "Default")
      (node (ref "LED1") (pin "C@3") (pinfunction "CBLUE_C@3") (pintype "passive"))
      (node (ref "R2") (pin "2") (pinfunction "2_2") (pintype "passive"))
    )
    (net (code "86") (name "Net-(LED1-CGREEN)") (class "Default")
      (node (ref "LED1") (pin "C@4") (pinfunction "CGREEN_C@4") (pintype "passive"))
      (node (ref "R3") (pin "2") (pinfunction "2_2") (pintype "passive"))
    )
    (net (code "87") (name "Net-(LED1-CRED)") (class "Default")
      (node (ref "LED1") (pin "C@1") (pinfunction "CRED_C@1") (pintype "passive"))
      (node (ref "R1") (pin "2") (pinfunction "2_2") (pintype "passive"))
    )
    (net (code "88") (name "Net-(LED2-CBLUE)") (class "Default")
      (node (ref "LED2") (pin "C@3") (pinfunction "CBLUE_C@3") (pintype "passive"))
      (node (ref "R5") (pin "2") (pinfunction "2_2") (pintype "passive"))
    )
    (net (code "89") (name "Net-(LED2-CGREEN)") (class "Default")
      (node (ref "LED2") (pin "C@4") (pinfunction "CGREEN_C@4") (pintype "passive"))
      (node (ref "R6") (pin "2") (pinfunction "2_2") (pintype "passive"))
    )
    (net (code "90") (name "Net-(LED2-CRED)") (class "Default")
      (node (ref "LED2") (pin "C@1") (pinfunction "CRED_C@1") (pintype "passive"))
      (node (ref "R4") (pin "2") (pinfunction "2_2") (pintype "passive"))
    )
    (net (code "91") (name "Net-(LED3-CBLUE)") (class "Default")
      (node (ref "LED3") (pin "C@3") (pinfunction "CBLUE_C@3") (pintype "passive"))
      (node (ref "R8") (pin "2") (pinfunction "2_2") (pintype "passive"))
    )
    (net (code "92") (name "Net-(LED3-CGREEN)") (class "Default")
      (node (ref "LED3") (pin "C@4") (pinfunction "CGREEN_C@4") (pintype "passive"))
      (node (ref "R9") (pin "2") (pinfunction "2_2") (pintype "passive"))
    )
    (net (code "93") (name "Net-(LED3-CRED)") (class "Default")
      (node (ref "LED3") (pin "C@1") (pinfunction "CRED_C@1") (pintype "passive"))
      (node (ref "R7") (pin "2") (pinfunction "2_2") (pintype "passive"))
    )
    (net (code "94") (name "Net-(LED4-CBLUE)") (class "Default")
      (node (ref "LED4") (pin "C@3") (pinfunction "CBLUE_C@3") (pintype "passive"))
      (node (ref "R11") (pin "2") (pinfunction "2_2") (pintype "passive"))
    )
    (net (code "95") (name "Net-(LED4-CGREEN)") (class "Default")
      (node (ref "LED4") (pin "C@4") (pinfunction "CGREEN_C@4") (pintype "passive"))
      (node (ref "R12") (pin "2") (pinfunction "2_2") (pintype "passive"))
    )
    (net (code "96") (name "Net-(LED4-CRED)") (class "Default")
      (node (ref "LED4") (pin "C@1") (pinfunction "CRED_C@1") (pintype "passive"))
      (node (ref "R10") (pin "2") (pinfunction "2_2") (pintype "passive"))
    )
    (net (code "97") (name "Net-(LED5-CBLUE)") (class "Default")
      (node (ref "LED5") (pin "C@3") (pinfunction "CBLUE_C@3") (pintype "passive"))
      (node (ref "R14") (pin "2") (pinfunction "2_2") (pintype "passive"))
    )
    (net (code "98") (name "Net-(LED5-CGREEN)") (class "Default")
      (node (ref "LED5") (pin "C@4") (pinfunction "CGREEN_C@4") (pintype "passive"))
      (node (ref "R15") (pin "2") (pinfunction "2_2") (pintype "passive"))
    )
    (net (code "99") (name "Net-(LED5-CRED)") (class "Default")
      (node (ref "LED5") (pin "C@1") (pinfunction "CRED_C@1") (pintype "passive"))
      (node (ref "R13") (pin "2") (pinfunction "2_2") (pintype "passive"))
    )
    (net (code "100") (name "Net-(LED6-CBLUE)") (class "Default")
      (node (ref "LED6") (pin "C@3") (pinfunction "CBLUE_C@3") (pintype "passive"))
      (node (ref "R17") (pin "2") (pinfunction "2_2") (pintype "passive"))
    )
    (net (code "101") (name "Net-(LED6-CGREEN)") (class "Default")
      (node (ref "LED6") (pin "C@4") (pinfunction "CGREEN_C@4") (pintype "passive"))
      (node (ref "R18") (pin "2") (pinfunction "2_2") (pintype "passive"))
    )
    (net (code "102") (name "Net-(LED6-CRED)") (class "Default")
      (node (ref "LED6") (pin "C@1") (pinfunction "CRED_C@1") (pintype "passive"))
      (node (ref "R16") (pin "2") (pinfunction "2_2") (pintype "passive"))
    )
    (net (code "103") (name "Net-(LED7-CBLUE)") (class "Default")
      (node (ref "LED7") (pin "C@3") (pinfunction "CBLUE_C@3") (pintype "passive"))
      (node (ref "R20") (pin "2") (pinfunction "2_2") (pintype "passive"))
    )
    (net (code "104") (name "Net-(LED7-CGREEN)") (class "Default")
      (node (ref "LED7") (pin "C@4") (pinfunction "CGREEN_C@4") (pintype "passive"))
      (node (ref "R21") (pin "2") (pinfunction "2_2") (pintype "passive"))
    )
    (net (code "105") (name "Net-(LED7-CRED)") (class "Default")
      (node (ref "LED7") (pin "C@1") (pinfunction "CRED_C@1") (pintype "passive"))
      (node (ref "R19") (pin "2") (pinfunction "2_2") (pintype "passive"))
    )
    (net (code "106") (name "Net-(LED8-CBLUE)") (class "Default")
      (node (ref "LED8") (pin "C@3") (pinfunction "CBLUE_C@3") (pintype "passive"))
      (node (ref "R23") (pin "2") (pinfunction "2_2") (pintype "passive"))
    )
    (net (code "107") (name "Net-(LED8-CGREEN)") (class "Default")
      (node (ref "LED8") (pin "C@4") (pinfunction "CGREEN_C@4") (pintype "passive"))
      (node (ref "R24") (pin "2") (pinfunction "2_2") (pintype "passive"))
    )
    (net (code "108") (name "Net-(LED8-CRED)") (class "Default")
      (node (ref "LED8") (pin "C@1") (pinfunction "CRED_C@1") (pintype "passive"))
      (node (ref "R22") (pin "2") (pinfunction "2_2") (pintype "passive"))
    )
    (net (code "109") (name "Net-(LED9-CBLUE)") (class "Default")
      (node (ref "LED9") (pin "C@3") (pinfunction "CBLUE_C@3") (pintype "passive"))
      (node (ref "R26") (pin "2") (pinfunction "2_2") (pintype "passive"))
    )
    (net (code "110") (name "Net-(LED9-CGREEN)") (class "Default")
      (node (ref "LED9") (pin "C@4") (pinfunction "CGREEN_C@4") (pintype "passive"))
      (node (ref "R27") (pin "2") (pinfunction "2_2") (pintype "passive"))
    )
    (net (code "111") (name "Net-(LED9-CRED)") (class "Default")
      (node (ref "LED9") (pin "C@1") (pinfunction "CRED_C@1") (pintype "passive"))
      (node (ref "R25") (pin "2") (pinfunction "2_2") (pintype "passive"))
    )
    (net (code "112") (name "Net-(LED10-CBLUE)") (class "Default")
      (node (ref "LED10") (pin "C@3") (pinfunction "CBLUE_C@3") (pintype "passive"))
      (node (ref "R29") (pin "2") (pinfunction "2_2") (pintype "passive"))
    )
    (net (code "113") (name "Net-(LED10-CGREEN)") (class "Default")
      (node (ref "LED10") (pin "C@4") (pinfunction "CGREEN_C@4") (pintype "passive"))
      (node (ref "R30") (pin "2") (pinfunction "2_2") (pintype "passive"))
    )
    (net (code "114") (name "Net-(LED10-CRED)") (class "Default")
      (node (ref "LED10") (pin "C@1") (pinfunction "CRED_C@1") (pintype "passive"))
      (node (ref "R28") (pin "2") (pinfunction "2_2") (pintype "passive"))
    )
    (net (code "115") (name "Net-(LED11-CBLUE)") (class "Default")
      (node (ref "LED11") (pin "C@3") (pinfunction "CBLUE_C@3") (pintype "passive"))
      (node (ref "R32") (pin "2") (pinfunction "2_2") (pintype "passive"))
    )
    (net (code "116") (name "Net-(LED11-CGREEN)") (class "Default")
      (node (ref "LED11") (pin "C@4") (pinfunction "CGREEN_C@4") (pintype "passive"))
      (node (ref "R33") (pin "2") (pinfunction "2_2") (pintype "passive"))
    )
    (net (code "117") (name "Net-(LED11-CRED)") (class "Default")
      (node (ref "LED11") (pin "C@1") (pinfunction "CRED_C@1") (pintype "passive"))
      (node (ref "R31") (pin "2") (pinfunction "2_2") (pintype "passive"))
    )
    (net (code "118") (name "Net-(LED12-CBLUE)") (class "Default")
      (node (ref "LED12") (pin "C@3") (pinfunction "CBLUE_C@3") (pintype "passive"))
      (node (ref "R35") (pin "2") (pinfunction "2_2") (pintype "passive"))
    )
    (net (code "119") (name "Net-(LED12-CGREEN)") (class "Default")
      (node (ref "LED12") (pin "C@4") (pinfunction "CGREEN_C@4") (pintype "passive"))
      (node (ref "R36") (pin "2") (pinfunction "2_2") (pintype "passive"))
    )
    (net (code "120") (name "Net-(LED12-CRED)") (class "Default")
      (node (ref "LED12") (pin "C@1") (pinfunction "CRED_C@1") (pintype "passive"))
      (node (ref "R34") (pin "2") (pinfunction "2_2") (pintype "passive"))
    )
    (net (code "121") (name "Net-(LED13-CBLUE)") (class "Default")
      (node (ref "LED13") (pin "C@3") (pinfunction "CBLUE_C@3") (pintype "passive"))
      (node (ref "R38") (pin "2") (pinfunction "2_2") (pintype "passive"))
    )
    (net (code "122") (name "Net-(LED13-CGREEN)") (class "Default")
      (node (ref "LED13") (pin "C@4") (pinfunction "CGREEN_C@4") (pintype "passive"))
      (node (ref "R39") (pin "2") (pinfunction "2_2") (pintype "passive"))
    )
    (net (code "123") (name "Net-(LED13-CRED)") (class "Default")
      (node (ref "LED13") (pin "C@1") (pinfunction "CRED_C@1") (pintype "passive"))
      (node (ref "R37") (pin "2") (pinfunction "2_2") (pintype "passive"))
    )
    (net (code "124") (name "Net-(LED14-CBLUE)") (class "Default")
      (node (ref "LED14") (pin "C@3") (pinfunction "CBLUE_C@3") (pintype "passive"))
      (node (ref "R41") (pin "2") (pinfunction "2_2") (pintype "passive"))
    )
    (net (code "125") (name "Net-(LED14-CGREEN)") (class "Default")
      (node (ref "LED14") (pin "C@4") (pinfunction "CGREEN_C@4") (pintype "passive"))
      (node (ref "R42") (pin "2") (pinfunction "2_2") (pintype "passive"))
    )
    (net (code "126") (name "Net-(LED14-CRED)") (class "Default")
      (node (ref "LED14") (pin "C@1") (pinfunction "CRED_C@1") (pintype "passive"))
      (node (ref "R40") (pin "2") (pinfunction "2_2") (pintype "passive"))
    )
    (net (code "127") (name "Net-(LED15-CBLUE)") (class "Default")
      (node (ref "LED15") (pin "C@3") (pinfunction "CBLUE_C@3") (pintype "passive"))
      (node (ref "R44") (pin "2") (pinfunction "2_2") (pintype "passive"))
    )
    (net (code "128") (name "Net-(LED15-CGREEN)") (class "Default")
      (node (ref "LED15") (pin "C@4") (pinfunction "CGREEN_C@4") (pintype "passive"))
      (node (ref "R45") (pin "2") (pinfunction "2_2") (pintype "passive"))
    )
    (net (code "129") (name "Net-(LED15-CRED)") (class "Default")
      (node (ref "LED15") (pin "C@1") (pinfunction "CRED_C@1") (pintype "passive"))
      (node (ref "R43") (pin "2") (pinfunction "2_2") (pintype "passive"))
    )
    (net (code "130") (name "Net-(LED16-CBLUE)") (class "Default")
      (node (ref "LED16") (pin "C@3") (pinfunction "CBLUE_C@3") (pintype "passive"))
      (node (ref "R47") (pin "2") (pinfunction "2_2") (pintype "passive"))
    )
    (net (code "131") (name "Net-(LED16-CGREEN)") (class "Default")
      (node (ref "LED16") (pin "C@4") (pinfunction "CGREEN_C@4") (pintype "passive"))
      (node (ref "R48") (pin "2") (pinfunction "2_2") (pintype "passive"))
    )
    (net (code "132") (name "Net-(LED16-CRED)") (class "Default")
      (node (ref "LED16") (pin "C@1") (pinfunction "CRED_C@1") (pintype "passive"))
      (node (ref "R46") (pin "2") (pinfunction "2_2") (pintype "passive"))
    )
    (net (code "133") (name "Net-(LED17-CBLUE)") (class "Default")
      (node (ref "LED17") (pin "C@3") (pinfunction "CBLUE_C@3") (pintype "passive"))
      (node (ref "R50") (pin "2") (pinfunction "2_2") (pintype "passive"))
    )
    (net (code "134") (name "Net-(LED17-CGREEN)") (class "Default")
      (node (ref "LED17") (pin "C@4") (pinfunction "CGREEN_C@4") (pintype "passive"))
      (node (ref "R51") (pin "2") (pinfunction "2_2") (pintype "passive"))
    )
    (net (code "135") (name "Net-(LED17-CRED)") (class "Default")
      (node (ref "LED17") (pin "C@1") (pinfunction "CRED_C@1") (pintype "passive"))
      (node (ref "R49") (pin "2") (pinfunction "2_2") (pintype "passive"))
    )
    (net (code "136") (name "Net-(LED18-CBLUE)") (class "Default")
      (node (ref "LED18") (pin "C@3") (pinfunction "CBLUE_C@3") (pintype "passive"))
      (node (ref "R53") (pin "2") (pinfunction "2_2") (pintype "passive"))
    )
    (net (code "137") (name "Net-(LED18-CGREEN)") (class "Default")
      (node (ref "LED18") (pin "C@4") (pinfunction "CGREEN_C@4") (pintype "passive"))
      (node (ref "R54") (pin "2") (pinfunction "2_2") (pintype "passive"))
    )
    (net (code "138") (name "Net-(LED18-CRED)") (class "Default")
      (node (ref "LED18") (pin "C@1") (pinfunction "CRED_C@1") (pintype "passive"))
      (node (ref "R52") (pin "2") (pinfunction "2_2") (pintype "passive"))
    )
    (net (code "139") (name "Net-(LED19-CBLUE)") (class "Default")
      (node (ref "LED19") (pin "C@3") (pinfunction "CBLUE_C@3") (pintype "passive"))
      (node (ref "R56") (pin "2") (pinfunction "2_2") (pintype "passive"))
    )
    (net (code "140") (name "Net-(LED19-CGREEN)") (class "Default")
      (node (ref "LED19") (pin "C@4") (pinfunction "CGREEN_C@4") (pintype "passive"))
      (node (ref "R57") (pin "2") (pinfunction "2_2") (pintype "passive"))
    )
    (net (code "141") (name "Net-(LED19-CRED)") (class "Default")
      (node (ref "LED19") (pin "C@1") (pinfunction "CRED_C@1") (pintype "passive"))
      (node (ref "R55") (pin "2") (pinfunction "2_2") (pintype "passive"))
    )
    (net (code "142") (name "Net-(LED20-CBLUE)") (class "Default")
      (node (ref "LED20") (pin "C@3") (pinfunction "CBLUE_C@3") (pintype "passive"))
      (node (ref "R59") (pin "2") (pinfunction "2_2") (pintype "passive"))
    )
    (net (code "143") (name "Net-(LED20-CGREEN)") (class "Default")
      (node (ref "LED20") (pin "C@4") (pinfunction "CGREEN_C@4") (pintype "passive"))
      (node (ref "R60") (pin "2") (pinfunction "2_2") (pintype "passive"))
    )
    (net (code "144") (name "Net-(LED20-CRED)") (class "Default")
      (node (ref "LED20") (pin "C@1") (pinfunction "CRED_C@1") (pintype "passive"))
      (node (ref "R58") (pin "2") (pinfunction "2_2") (pintype "passive"))
    )
    (net (code "145") (name "Net-(LED21-CBLUE)") (class "Default")
      (node (ref "LED21") (pin "C@3") (pinfunction "CBLUE_C@3") (pintype "passive"))
      (node (ref "R62") (pin "2") (pinfunction "2_2") (pintype "passive"))
    )
    (net (code "146") (name "Net-(LED21-CGREEN)") (class "Default")
      (node (ref "LED21") (pin "C@4") (pinfunction "CGREEN_C@4") (pintype "passive"))
      (node (ref "R63") (pin "2") (pinfunction "2_2") (pintype "passive"))
    )
    (net (code "147") (name "Net-(LED21-CRED)") (class "Default")
      (node (ref "LED21") (pin "C@1") (pinfunction "CRED_C@1") (pintype "passive"))
      (node (ref "R61") (pin "2") (pinfunction "2_2") (pintype "passive"))
    )
    (net (code "148") (name "Net-(LED22-CBLUE)") (class "Default")
      (node (ref "LED22") (pin "C@3") (pinfunction "CBLUE_C@3") (pintype "passive"))
      (node (ref "R65") (pin "2") (pinfunction "2_2") (pintype "passive"))
    )
    (net (code "149") (name "Net-(LED22-CGREEN)") (class "Default")
      (node (ref "LED22") (pin "C@4") (pinfunction "CGREEN_C@4") (pintype "passive"))
      (node (ref "R66") (pin "2") (pinfunction "2_2") (pintype "passive"))
    )
    (net (code "150") (name "Net-(LED22-CRED)") (class "Default")
      (node (ref "LED22") (pin "C@1") (pinfunction "CRED_C@1") (pintype "passive"))
      (node (ref "R64") (pin "2") (pinfunction "2_2") (pintype "passive"))
    )
    (net (code "151") (name "Net-(LED23-CBLUE)") (class "Default")
      (node (ref "LED23") (pin "C@3") (pinfunction "CBLUE_C@3") (pintype "passive"))
      (node (ref "R68") (pin "2") (pinfunction "2_2") (pintype "passive"))
    )
    (net (code "152") (name "Net-(LED23-CGREEN)") (class "Default")
      (node (ref "LED23") (pin "C@4") (pinfunction "CGREEN_C@4") (pintype "passive"))
      (node (ref "R69") (pin "2") (pinfunction "2_2") (pintype "passive"))
    )
    (net (code "153") (name "Net-(LED23-CRED)") (class "Default")
      (node (ref "LED23") (pin "C@1") (pinfunction "CRED_C@1") (pintype "passive"))
      (node (ref "R67") (pin "2") (pinfunction "2_2") (pintype "passive"))
    )
    (net (code "154") (name "Net-(LED24-CBLUE)") (class "Default")
      (node (ref "LED24") (pin "C@3") (pinfunction "CBLUE_C@3") (pintype "passive"))
      (node (ref "R71") (pin "2") (pinfunction "2_2") (pintype "passive"))
    )
    (net (code "155") (name "Net-(LED24-CGREEN)") (class "Default")
      (node (ref "LED24") (pin "C@4") (pinfunction "CGREEN_C@4") (pintype "passive"))
      (node (ref "R72") (pin "2") (pinfunction "2_2") (pintype "passive"))
    )
    (net (code "156") (name "Net-(LED24-CRED)") (class "Default")
      (node (ref "LED24") (pin "C@1") (pinfunction "CRED_C@1") (pintype "passive"))
      (node (ref "R70") (pin "2") (pinfunction "2_2") (pintype "passive"))
    )
    (net (code "157") (name "Net-(U1-*D3)") (class "Default")
      (node (ref "S2") (pin "1") (pinfunction "1_1") (pintype "passive"))
      (node (ref "S2") (pin "2") (pinfunction "2_2") (pintype "passive"))
      (node (ref "U1") (pin "D3") (pinfunction "*D3_D3") (pintype "bidirectional"))
    )
    (net (code "158") (name "VCC") (class "Default")
      (node (ref "IC1") (pin "10") (pinfunction "SCL_10") (pintype "input"))
      (node (ref "IC2") (pin "10") (pinfunction "SCL_10") (pintype "input"))
      (node (ref "IC3") (pin "10") (pinfunction "SCL_10") (pintype "input"))
      (node (ref "IC4") (pin "10") (pinfunction "SCL_10") (pintype "input"))
      (node (ref "IC5") (pin "10") (pinfunction "SCL_10") (pintype "input"))
      (node (ref "IC6") (pin "10") (pinfunction "SCL_10") (pintype "input"))
      (node (ref "IC7") (pin "10") (pinfunction "SCL_10") (pintype "input"))
      (node (ref "IC8") (pin "10") (pinfunction "SCL_10") (pintype "input"))
      (node (ref "IC9") (pin "10") (pinfunction "SCL_10") (pintype "input"))
      (node (ref "LED1") (pin "A") (pinfunction "A2_A") (pintype "passive"))
      (node (ref "LED10") (pin "A") (pinfunction "A2_A") (pintype "passive"))
      (node (ref "LED11") (pin "A") (pinfunction "A2_A") (pintype "passive"))
      (node (ref "LED12") (pin "A") (pinfunction "A2_A") (pintype "passive"))
      (node (ref "LED13") (pin "A") (pinfunction "A2_A") (pintype "passive"))
      (node (ref "LED14") (pin "A") (pinfunction "A2_A") (pintype "passive"))
      (node (ref "LED15") (pin "A") (pinfunction "A2_A") (pintype "passive"))
      (node (ref "LED16") (pin "A") (pinfunction "A2_A") (pintype "passive"))
      (node (ref "LED17") (pin "A") (pinfunction "A2_A") (pintype "passive"))
      (node (ref "LED18") (pin "A") (pinfunction "A2_A") (pintype "passive"))
      (node (ref "LED19") (pin "A") (pinfunction "A2_A") (pintype "passive"))
      (node (ref "LED2") (pin "A") (pinfunction "A2_A") (pintype "passive"))
      (node (ref "LED20") (pin "A") (pinfunction "A2_A") (pintype "passive"))
      (node (ref "LED21") (pin "A") (pinfunction "A2_A") (pintype "passive"))
      (node (ref "LED22") (pin "A") (pinfunction "A2_A") (pintype "passive"))
      (node (ref "LED23") (pin "A") (pinfunction "A2_A") (pintype "passive"))
      (node (ref "LED24") (pin "A") (pinfunction "A2_A") (pintype "passive"))
      (node (ref "LED3") (pin "A") (pinfunction "A2_A") (pintype "passive"))
      (node (ref "LED4") (pin "A") (pinfunction "A2_A") (pintype "passive"))
      (node (ref "LED5") (pin "A") (pinfunction "A2_A") (pintype "passive"))
      (node (ref "LED6") (pin "A") (pinfunction "A2_A") (pintype "passive"))
      (node (ref "LED7") (pin "A") (pinfunction "A2_A") (pintype "passive"))
      (node (ref "LED8") (pin "A") (pinfunction "A2_A") (pintype "passive"))
      (node (ref "LED9") (pin "A") (pinfunction "A2_A") (pintype "passive"))
      (node (ref "U1") (pin "VIN") (pinfunction "VIN_VIN") (pintype "bidirectional"))
    )
    (net (code "159") (name "unconnected-(IC2A-QH*-Pad9)") (class "Default")
      (node (ref "IC2") (pin "9") (pinfunction "QH*_9") (pintype "tri_state"))
    )
    (net (code "160") (name "unconnected-(U1-*D5-PadD5)") (class "Default")
      (node (ref "U1") (pin "D5") (pinfunction "*D5_D5") (pintype "bidirectional"))
    )
    (net (code "161") (name "unconnected-(U1-*D6-PadD6)") (class "Default")
      (node (ref "U1") (pin "D6") (pinfunction "*D6_D6") (pintype "bidirectional"))
    )
    (net (code "162") (name "unconnected-(U1-*D9-PadD9)") (class "Default")
      (node (ref "U1") (pin "D9") (pinfunction "*D9_D9") (pintype "bidirectional"))
    )
    (net (code "163") (name "unconnected-(U1-*D10-PadD10)") (class "Default")
      (node (ref "U1") (pin "D10") (pinfunction "*D10_D10") (pintype "bidirectional"))
    )
    (net (code "164") (name "unconnected-(U1-GND-PadGND@2)") (class "Default")
      (node (ref "U1") (pin "GND@2") (pinfunction "GND_GND@2") (pintype "bidirectional"))
    )
    (net (code "165") (name "unconnected-(U1-Pad3.3V)") (class "Default")
      (node (ref "U1") (pin "3.3V") (pinfunction "3.3V_3.3V") (pintype "bidirectional"))
    )
    (net (code "166") (name "unconnected-(U1-Pad5V)") (class "Default")
      (node (ref "U1") (pin "5V") (pinfunction "5V_5V") (pintype "bidirectional"))
    )
    (net (code "167") (name "unconnected-(U1-PadA0)") (class "Default")
      (node (ref "U1") (pin "A0") (pinfunction "A0_A0") (pintype "bidirectional"))
    )
    (net (code "168") (name "unconnected-(U1-PadA1)") (class "Default")
      (node (ref "U1") (pin "A1") (pinfunction "A1_A1") (pintype "bidirectional"))
    )
    (net (code "169") (name "unconnected-(U1-PadA2)") (class "Default")
      (node (ref "U1") (pin "A2") (pinfunction "A2_A2") (pintype "bidirectional"))
    )
    (net (code "170") (name "unconnected-(U1-PadA3)") (class "Default")
      (node (ref "U1") (pin "A3") (pinfunction "A3_A3") (pintype "bidirectional"))
    )
    (net (code "171") (name "unconnected-(U1-PadA4)") (class "Default")
      (node (ref "U1") (pin "A4") (pinfunction "A4_A4") (pintype "bidirectional"))
    )
    (net (code "172") (name "unconnected-(U1-PadA5)") (class "Default")
      (node (ref "U1") (pin "A5") (pinfunction "A5_A5") (pintype "bidirectional"))
    )
    (net (code "173") (name "unconnected-(U1-PadAREF)") (class "Default")
      (node (ref "U1") (pin "AREF") (pinfunction "AREF_AREF") (pintype "bidirectional"))
    )
    (net (code "174") (name "unconnected-(U1-PadD2)") (class "Default")
      (node (ref "U1") (pin "D2") (pinfunction "D2_D2") (pintype "bidirectional"))
    )
    (net (code "175") (name "unconnected-(U1-PadD4)") (class "Default")
      (node (ref "U1") (pin "D4") (pinfunction "D4_D4") (pintype "bidirectional"))
    )
    (net (code "176") (name "unconnected-(U1-PadD7)") (class "Default")
      (node (ref "U1") (pin "D7") (pinfunction "D7_D7") (pintype "bidirectional"))
    )
    (net (code "177") (name "unconnected-(U1-PadD12)") (class "Default")
      (node (ref "U1") (pin "D12") (pinfunction "D12_D12") (pintype "bidirectional"))
    )
    (net (code "178") (name "unconnected-(U1-PadRES)") (class "Default")
      (node (ref "U1") (pin "RES") (pinfunction "RES_RES") (pintype "bidirectional"))
    )
    (net (code "179") (name "unconnected-(U1-PadRX)") (class "Default")
      (node (ref "U1") (pin "RX") (pinfunction "RX_RX") (pintype "bidirectional"))
    )
    (net (code "180") (name "unconnected-(U1-PadTX)") (class "Default")
      (node (ref "U1") (pin "TX") (pinfunction "TX_TX") (pintype "bidirectional"))
    )
  )
)
